# Sheet_1.net
KiCad netlist of a schematic drawn in EasyEDA
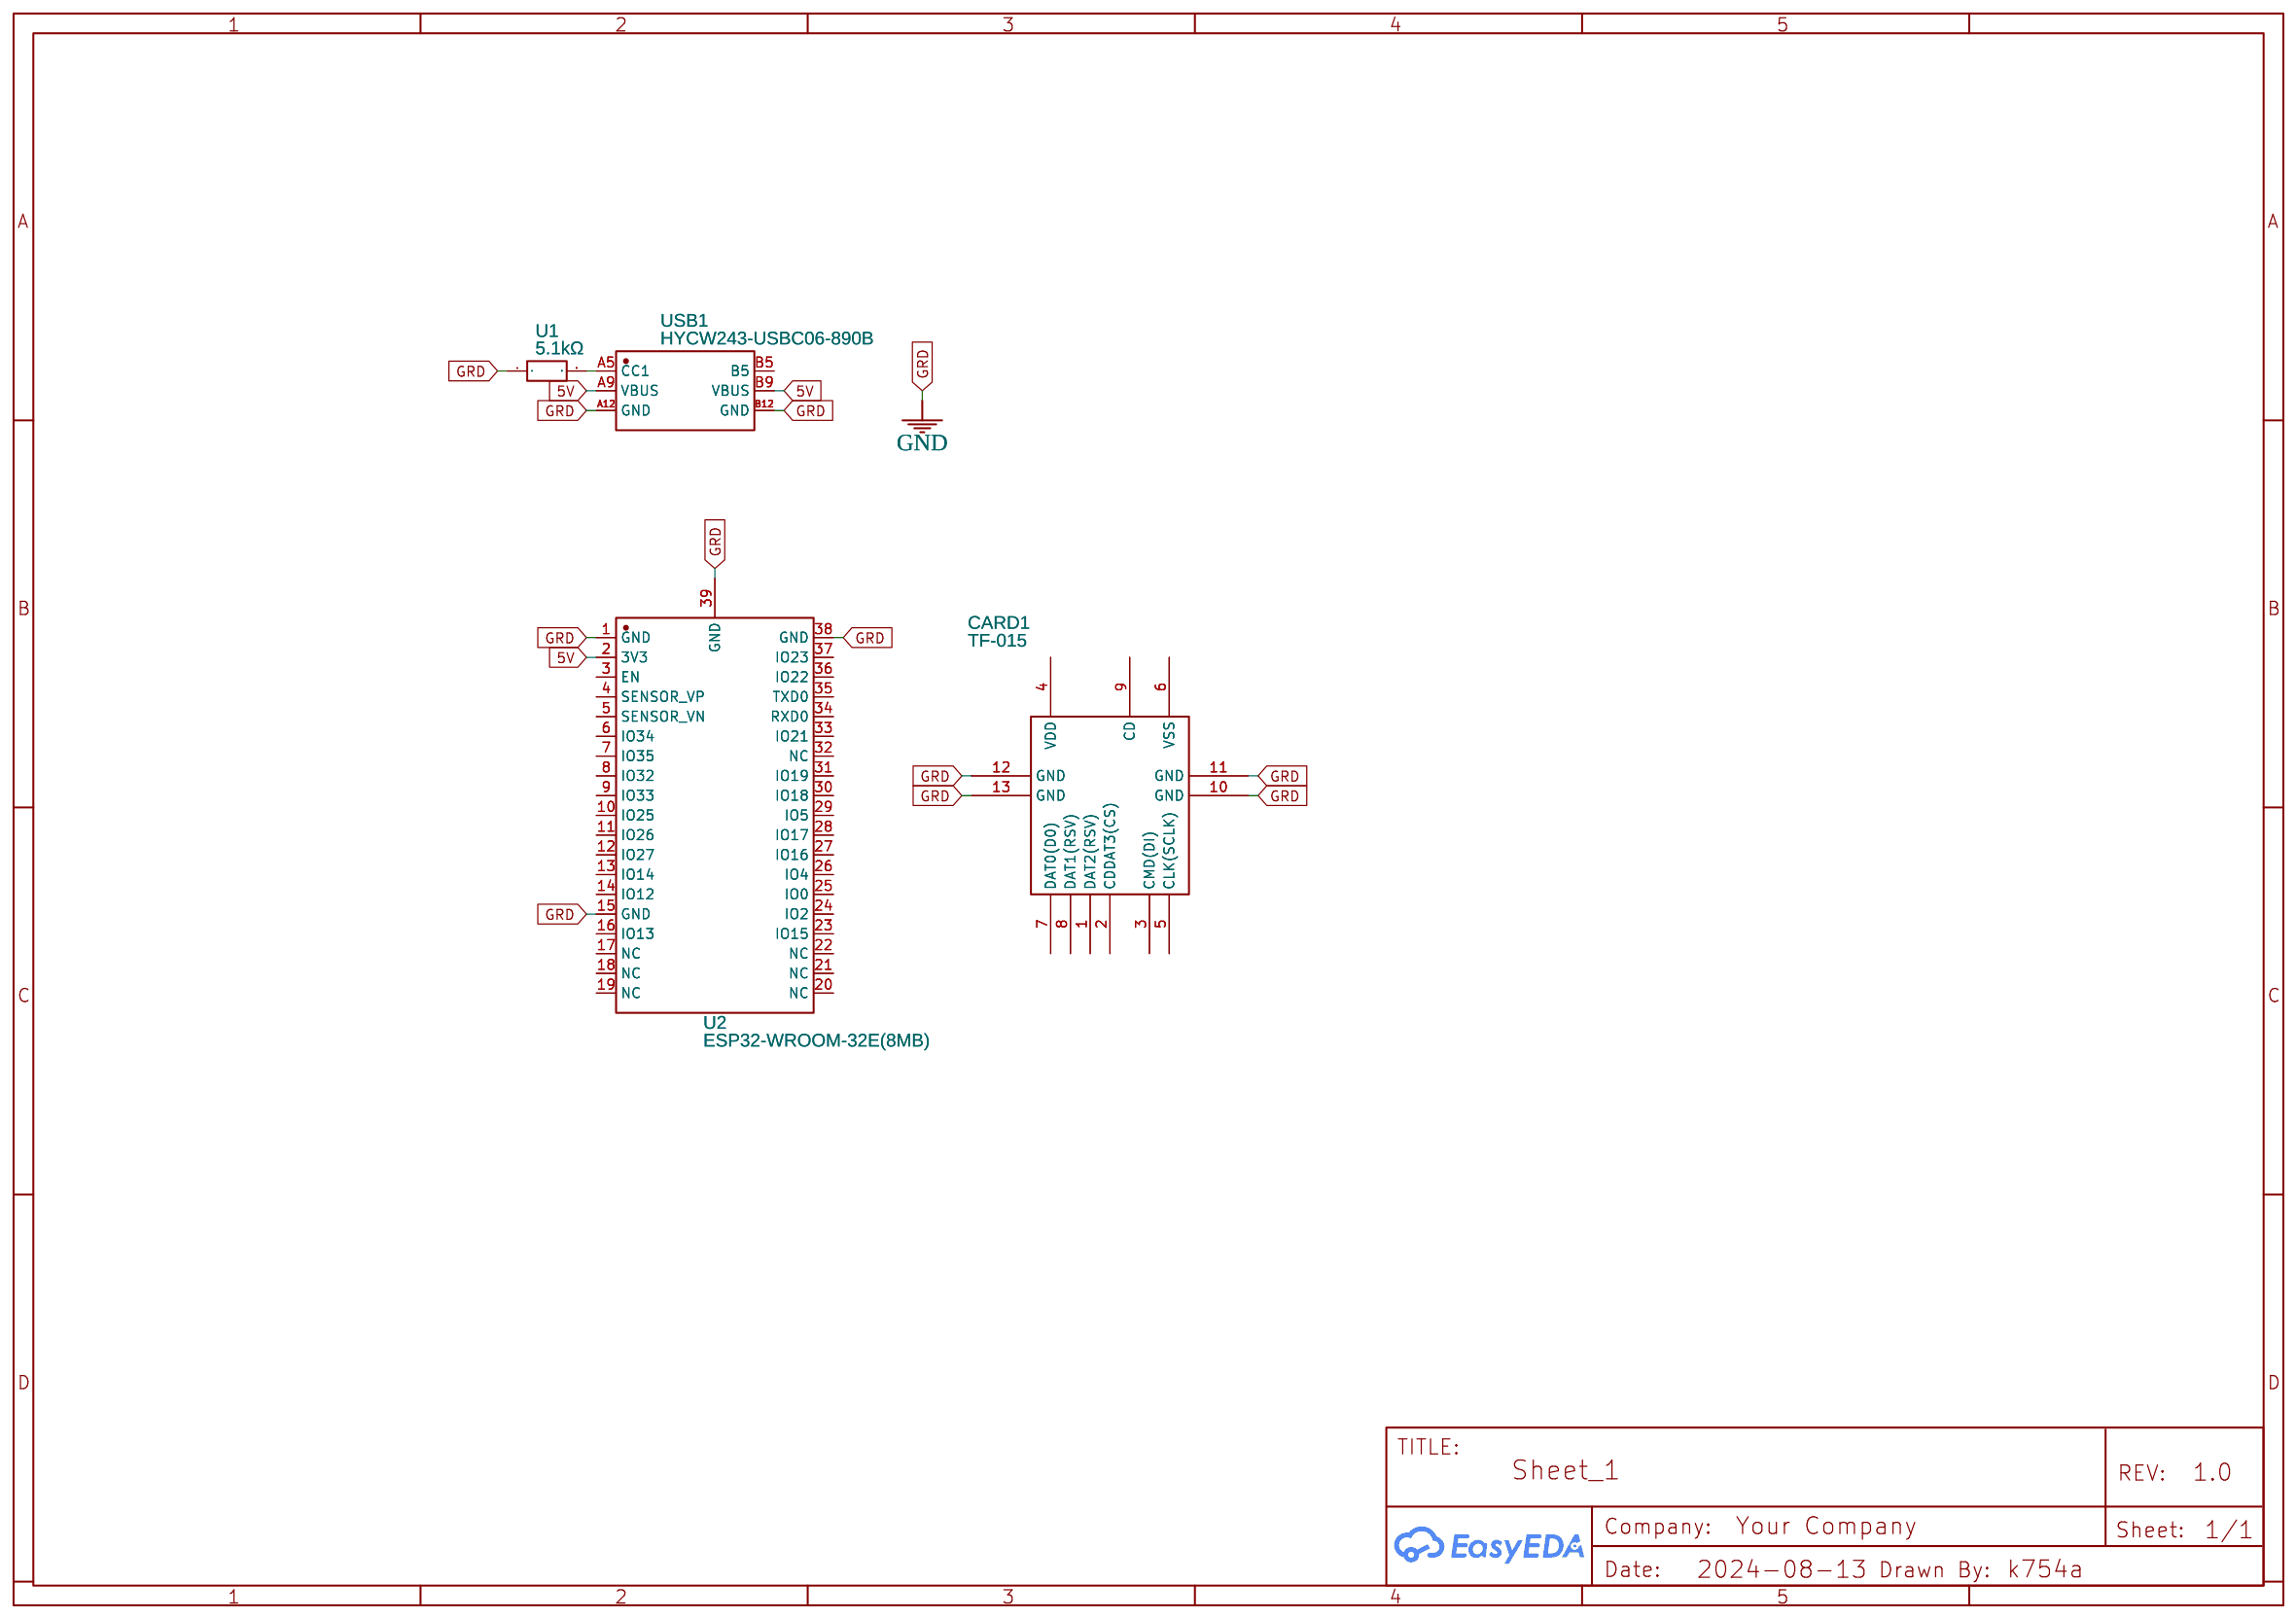
[diagram p0: schematic sheet]

(export (version "E")
  (design (tool "Eeschema 10.0.6"))
  (components
    (comp (ref "CARD1")
      (value "TF-015")
      (fields (field (name "Manufacturer") "SOFNG(硕方)"))
      (libsource (lib "") (part "TF-015"))
    )
    (comp (ref "U1")
      (value "5.1kΩ")
      (fields (field (name "Manufacturer Part") "CR1/8W-5K1±5%-ST52") (field (name "Manufacturer") "VO(翔胜)"))
      (libsource (lib "") (part "CR1/8W-5K1±5%-ST52"))
    )
    (comp (ref "U2")
      (value "ESP32-WROOM-32E(8MB)")
      (fields
        (field (name "Manufacturer Part") "ESP32-WROOM-32E-N8")
        (field (name "Manufacturer") "ESPRESSIF(乐鑫)")
      )
      (libsource (lib "") (part "ESP32-WROOM-32E(8MB)"))
    )
    (comp (ref "USB1")
      (value "HYCW243-USBC06-890B")
      (fields (field (name "Manufacturer") "华宇创"))
      (libsource (lib "") (part "HYCW243-USBC06-890B"))
    )
  )
  (nets
    (net (code "1") (name "5V") (class "Default")
      (node (ref "U2") (pin "2") (pinfunction "3V3_2") (pintype "unspecified"))
      (node (ref "USB1") (pin "A9") (pinfunction "VBUS_A9") (pintype "unspecified"))
      (node (ref "USB1") (pin "B9") (pinfunction "VBUS_B9") (pintype "unspecified"))
    )
    (net (code "2") (name "GRD") (class "Default")
      (node (ref "CARD1") (pin "10") (pinfunction "GND_10") (pintype "input"))
      (node (ref "CARD1") (pin "11") (pinfunction "GND_11") (pintype "input"))
      (node (ref "CARD1") (pin "12") (pinfunction "GND_12") (pintype "input"))
      (node (ref "CARD1") (pin "13") (pinfunction "GND_13") (pintype "input"))
      (node (ref "U1") (pin "1") (pinfunction "1_1") (pintype "unspecified"))
      (node (ref "U2") (pin "1") (pinfunction "GND_1") (pintype "unspecified"))
      (node (ref "U2") (pin "15") (pinfunction "GND_15") (pintype "unspecified"))
      (node (ref "U2") (pin "38") (pinfunction "GND_38") (pintype "unspecified"))
      (node (ref "U2") (pin "39") (pinfunction "GND_39") (pintype "unspecified"))
      (node (ref "USB1") (pin "A12") (pinfunction "GND_A12") (pintype "unspecified"))
      (node (ref "USB1") (pin "B12") (pinfunction "GND_B12") (pintype "unspecified"))
    )
    (net (code "3") (name "Net-(USB1-CC1)") (class "Default")
      (node (ref "U1") (pin "2") (pinfunction "2_2") (pintype "unspecified"))
      (node (ref "USB1") (pin "A5") (pinfunction "CC1_A5") (pintype "unspecified"))
    )
    (net (code "4") (name "unconnected-(CARD1-CD-Pad9)") (class "Default")
      (node (ref "CARD1") (pin "9") (pinfunction "CD_9") (pintype "input"))
    )
    (net (code "5") (name "unconnected-(CARD1-CDDAT3(CS)-Pad2)") (class "Default")
      (node (ref "CARD1") (pin "2") (pinfunction "CDDAT3(CS)_2") (pintype "bidirectional"))
    )
    (net (code "6") (name "unconnected-(CARD1-CLK(SCLK)-Pad5)") (class "Default")
      (node (ref "CARD1") (pin "5") (pinfunction "CLK(SCLK)_5") (pintype "input"))
    )
    (net (code "7") (name "unconnected-(CARD1-CMD(DI)-Pad3)") (class "Default")
      (node (ref "CARD1") (pin "3") (pinfunction "CMD(DI)_3") (pintype "input"))
    )
    (net (code "8") (name "unconnected-(CARD1-DAT0(D0)-Pad7)") (class "Default")
      (node (ref "CARD1") (pin "7") (pinfunction "DAT0(D0)_7") (pintype "bidirectional"))
    )
    (net (code "9") (name "unconnected-(CARD1-DAT1(RSV)-Pad8)") (class "Default")
      (node (ref "CARD1") (pin "8") (pinfunction "DAT1(RSV)_8") (pintype "bidirectional"))
    )
    (net (code "10") (name "unconnected-(CARD1-DAT2(RSV)-Pad1)") (class "Default")
      (node (ref "CARD1") (pin "1") (pinfunction "DAT2(RSV)_1") (pintype "bidirectional"))
    )
    (net (code "11") (name "unconnected-(CARD1-VDD-Pad4)") (class "Default")
      (node (ref "CARD1") (pin "4") (pinfunction "VDD_4") (pintype "input"))
    )
    (net (code "12") (name "unconnected-(CARD1-VSS-Pad6)") (class "Default")
      (node (ref "CARD1") (pin "6") (pinfunction "VSS_6") (pintype "input"))
    )
    (net (code "13") (name "unconnected-(U2-EN-Pad3)") (class "Default")
      (node (ref "U2") (pin "3") (pinfunction "EN_3") (pintype "unspecified"))
    )
    (net (code "14") (name "unconnected-(U2-IO0-Pad25)") (class "Default")
      (node (ref "U2") (pin "25") (pinfunction "IO0_25") (pintype "unspecified"))
    )
    (net (code "15") (name "unconnected-(U2-IO2-Pad24)") (class "Default")
      (node (ref "U2") (pin "24") (pinfunction "IO2_24") (pintype "unspecified"))
    )
    (net (code "16") (name "unconnected-(U2-IO4-Pad26)") (class "Default")
      (node (ref "U2") (pin "26") (pinfunction "IO4_26") (pintype "unspecified"))
    )
    (net (code "17") (name "unconnected-(U2-IO5-Pad29)") (class "Default")
      (node (ref "U2") (pin "29") (pinfunction "IO5_29") (pintype "unspecified"))
    )
    (net (code "18") (name "unconnected-(U2-IO12-Pad14)") (class "Default")
      (node (ref "U2") (pin "14") (pinfunction "IO12_14") (pintype "unspecified"))
    )
    (net (code "19") (name "unconnected-(U2-IO13-Pad16)") (class "Default")
      (node (ref "U2") (pin "16") (pinfunction "IO13_16") (pintype "unspecified"))
    )
    (net (code "20") (name "unconnected-(U2-IO14-Pad13)") (class "Default")
      (node (ref "U2") (pin "13") (pinfunction "IO14_13") (pintype "unspecified"))
    )
    (net (code "21") (name "unconnected-(U2-IO15-Pad23)") (class "Default")
      (node (ref "U2") (pin "23") (pinfunction "IO15_23") (pintype "unspecified"))
    )
    (net (code "22") (name "unconnected-(U2-IO16-Pad27)") (class "Default")
      (node (ref "U2") (pin "27") (pinfunction "IO16_27") (pintype "unspecified"))
    )
    (net (code "23") (name "unconnected-(U2-IO17-Pad28)") (class "Default")
      (node (ref "U2") (pin "28") (pinfunction "IO17_28") (pintype "unspecified"))
    )
    (net (code "24") (name "unconnected-(U2-IO18-Pad30)") (class "Default")
      (node (ref "U2") (pin "30") (pinfunction "IO18_30") (pintype "unspecified"))
    )
    (net (code "25") (name "unconnected-(U2-IO19-Pad31)") (class "Default")
      (node (ref "U2") (pin "31") (pinfunction "IO19_31") (pintype "unspecified"))
    )
    (net (code "26") (name "unconnected-(U2-IO21-Pad33)") (class "Default")
      (node (ref "U2") (pin "33") (pinfunction "IO21_33") (pintype "unspecified"))
    )
    (net (code "27") (name "unconnected-(U2-IO22-Pad36)") (class "Default")
      (node (ref "U2") (pin "36") (pinfunction "IO22_36") (pintype "unspecified"))
    )
    (net (code "28") (name "unconnected-(U2-IO23-Pad37)") (class "Default")
      (node (ref "U2") (pin "37") (pinfunction "IO23_37") (pintype "unspecified"))
    )
    (net (code "29") (name "unconnected-(U2-IO25-Pad10)") (class "Default")
      (node (ref "U2") (pin "10") (pinfunction "IO25_10") (pintype "unspecified"))
    )
    (net (code "30") (name "unconnected-(U2-IO26-Pad11)") (class "Default")
      (node (ref "U2") (pin "11") (pinfunction "IO26_11") (pintype "unspecified"))
    )
    (net (code "31") (name "unconnected-(U2-IO27-Pad12)") (class "Default")
      (node (ref "U2") (pin "12") (pinfunction "IO27_12") (pintype "unspecified"))
    )
    (net (code "32") (name "unconnected-(U2-IO32-Pad8)") (class "Default")
      (node (ref "U2") (pin "8") (pinfunction "IO32_8") (pintype "unspecified"))
    )
    (net (code "33") (name "unconnected-(U2-IO33-Pad9)") (class "Default")
      (node (ref "U2") (pin "9") (pinfunction "IO33_9") (pintype "unspecified"))
    )
    (net (code "34") (name "unconnected-(U2-IO34-Pad6)") (class "Default")
      (node (ref "U2") (pin "6") (pinfunction "IO34_6") (pintype "unspecified"))
    )
    (net (code "35") (name "unconnected-(U2-IO35-Pad7)") (class "Default")
      (node (ref "U2") (pin "7") (pinfunction "IO35_7") (pintype "unspecified"))
    )
    (net (code "36") (name "unconnected-(U2-NC-Pad17)") (class "Default")
      (node (ref "U2") (pin "17") (pinfunction "NC_17") (pintype "unspecified"))
    )
    (net (code "37") (name "unconnected-(U2-NC-Pad18)") (class "Default")
      (node (ref "U2") (pin "18") (pinfunction "NC_18") (pintype "unspecified"))
    )
    (net (code "38") (name "unconnected-(U2-NC-Pad19)") (class "Default")
      (node (ref "U2") (pin "19") (pinfunction "NC_19") (pintype "unspecified"))
    )
    (net (code "39") (name "unconnected-(U2-NC-Pad20)") (class "Default")
      (node (ref "U2") (pin "20") (pinfunction "NC_20") (pintype "unspecified"))
    )
    (net (code "40") (name "unconnected-(U2-NC-Pad21)") (class "Default")
      (node (ref "U2") (pin "21") (pinfunction "NC_21") (pintype "unspecified"))
    )
    (net (code "41") (name "unconnected-(U2-NC-Pad22)") (class "Default")
      (node (ref "U2") (pin "22") (pinfunction "NC_22") (pintype "unspecified"))
    )
    (net (code "42") (name "unconnected-(U2-NC-Pad32)") (class "Default")
      (node (ref "U2") (pin "32") (pinfunction "NC_32") (pintype "unspecified"))
    )
    (net (code "43") (name "unconnected-(U2-RXD0-Pad34)") (class "Default")
      (node (ref "U2") (pin "34") (pinfunction "RXD0_34") (pintype "unspecified"))
    )
    (net (code "44") (name "unconnected-(U2-SENSOR_VN-Pad5)") (class "Default")
      (node (ref "U2") (pin "5") (pinfunction "SENSOR_VN_5") (pintype "unspecified"))
    )
    (net (code "45") (name "unconnected-(U2-SENSOR_VP-Pad4)") (class "Default")
      (node (ref "U2") (pin "4") (pinfunction "SENSOR_VP_4") (pintype "unspecified"))
    )
    (net (code "46") (name "unconnected-(U2-TXD0-Pad35)") (class "Default")
      (node (ref "U2") (pin "35") (pinfunction "TXD0_35") (pintype "unspecified"))
    )
    (net (code "47") (name "unconnected-(USB1-PadB5)") (class "Default")
      (node (ref "USB1") (pin "B5") (pinfunction "B5_B5") (pintype "unspecified"))
    )
  )
)
